# SolarCharger.net
KiCad netlist of a schematic drawn in Altium Designer
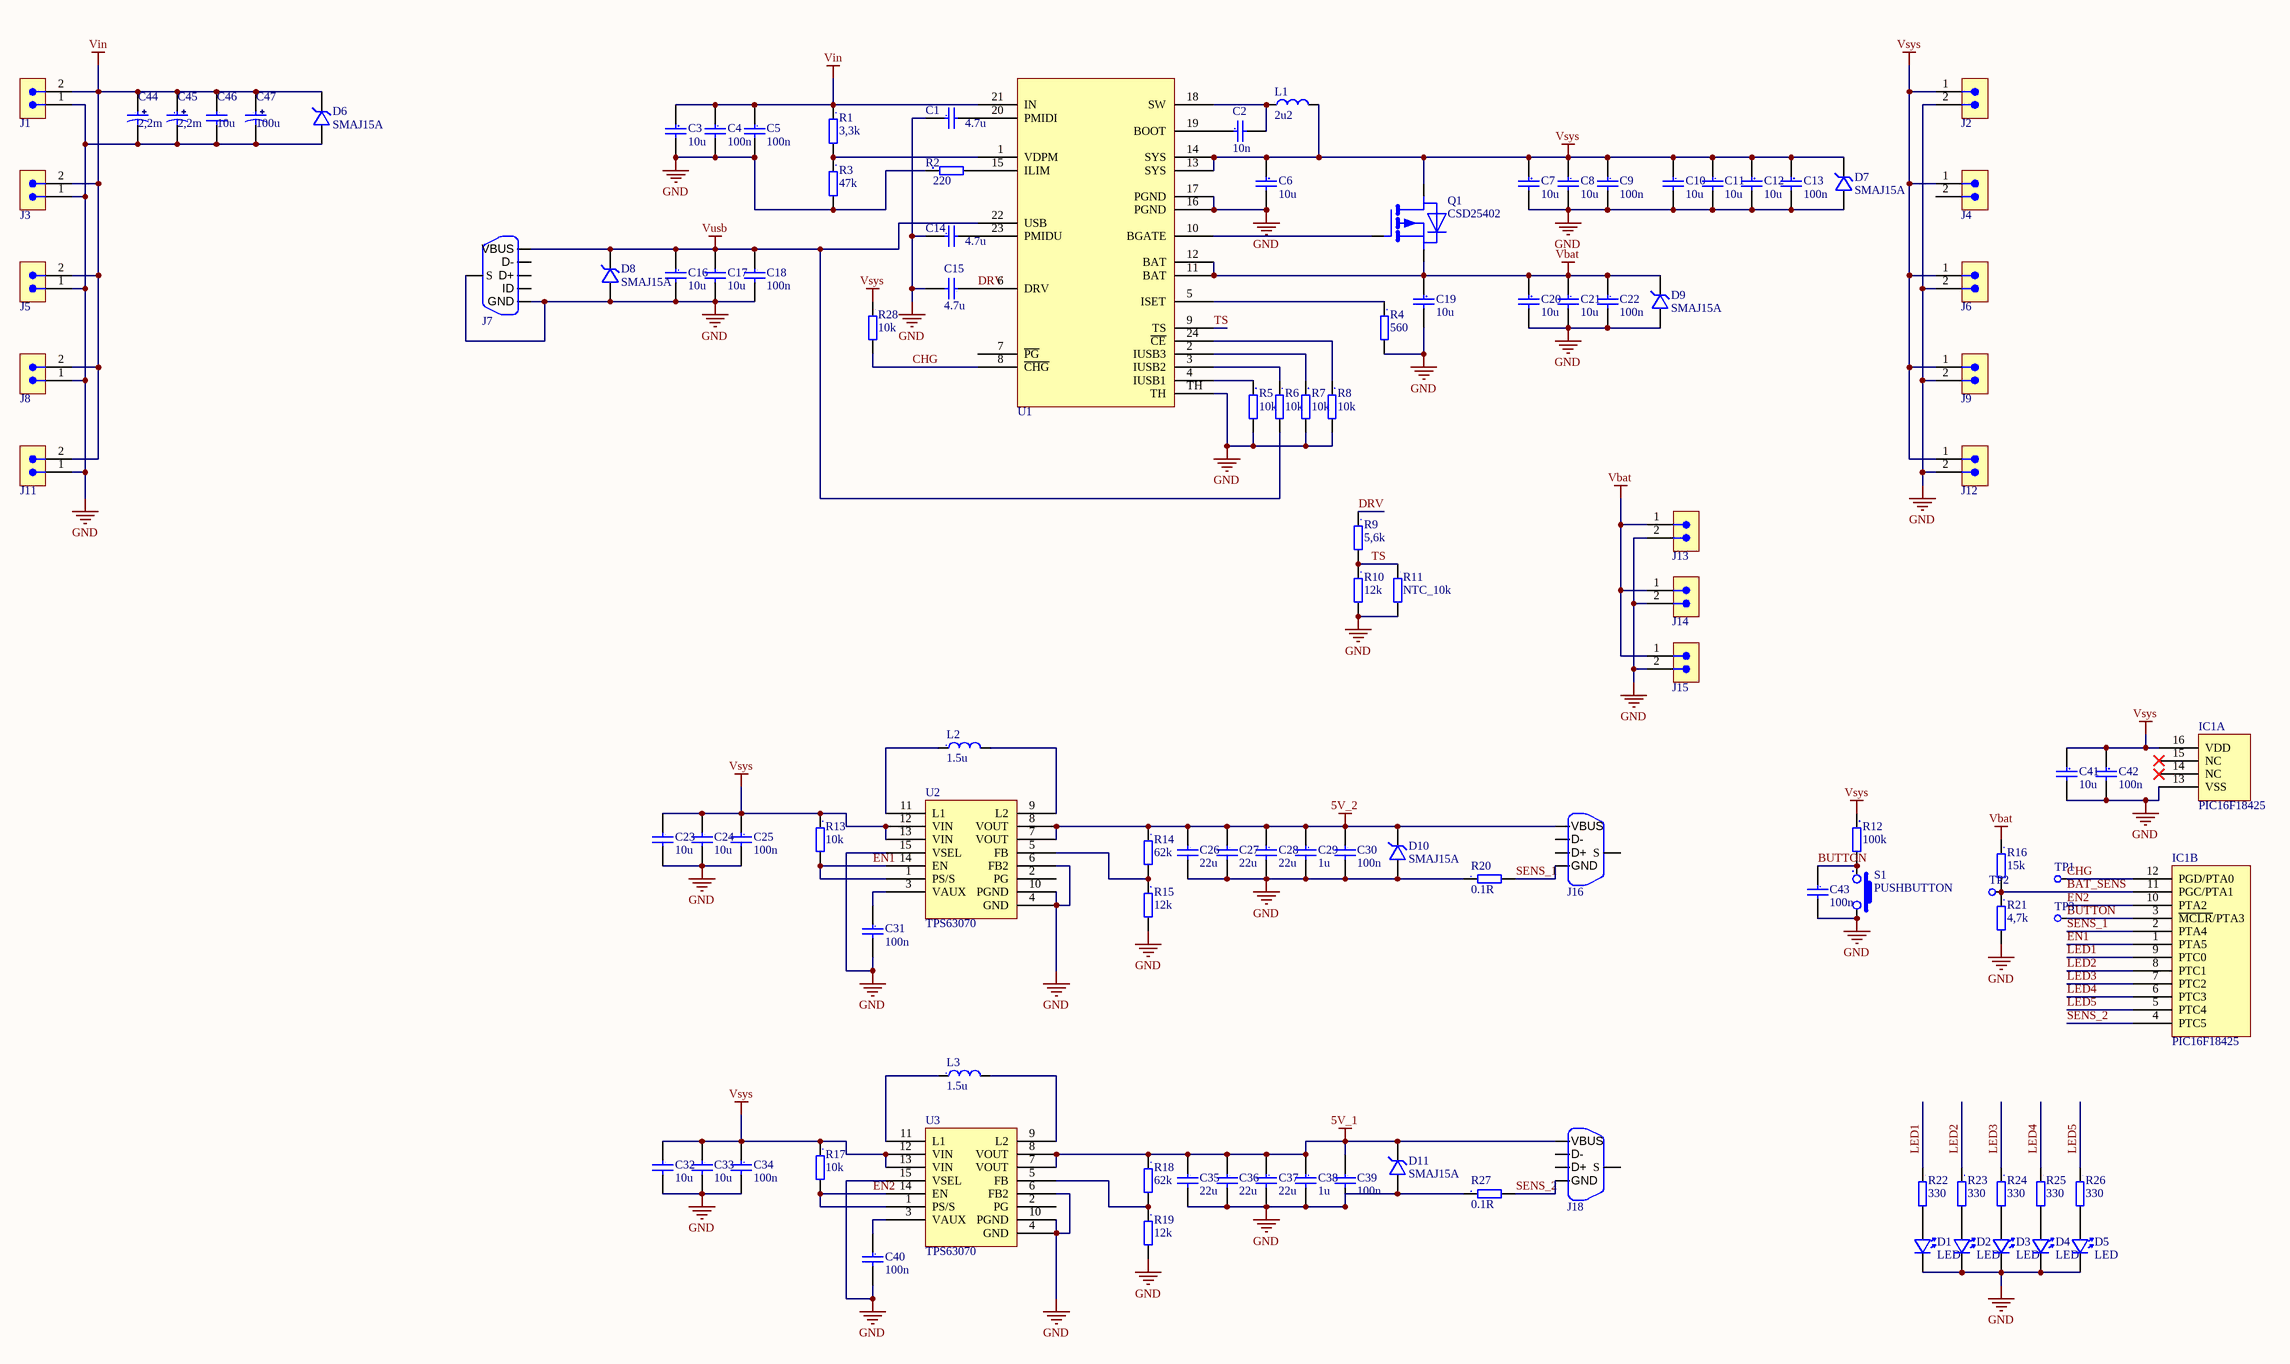
[diagram p0: SolarCharger.SchDoc]

(export (version "E")
  (design (tool "Eeschema 10.0.6"))
  (components
    (comp (ref "C1") (value "4.7u") (footprint "C0603_N") (libsource (lib "MyLib") (part "CAP")))
    (comp (ref "C2") (value "10n") (footprint "C0603_N") (libsource (lib "MyLib") (part "CAP")))
    (comp (ref "C3") (value "10u") (footprint "C0805_N") (libsource (lib "MyLib") (part "CAP")))
    (comp (ref "C4") (value "100n") (footprint "C0603_N") (libsource (lib "MyLib") (part "CAP")))
    (comp (ref "C5") (value "100n") (footprint "C0603_N") (libsource (lib "MyLib") (part "CAP")))
    (comp (ref "C6") (value "10u") (footprint "C0805_N") (libsource (lib "MyLib") (part "CAP")))
    (comp (ref "C7") (value "10u") (footprint "C0805_N") (libsource (lib "MyLib") (part "CAP")))
    (comp (ref "C8") (value "10u") (footprint "C0805_N") (libsource (lib "MyLib") (part "CAP")))
    (comp (ref "C9") (value "100n") (footprint "C0603_N") (libsource (lib "MyLib") (part "CAP")))
    (comp (ref "C10") (value "10u") (footprint "C0805_N") (libsource (lib "MyLib") (part "CAP")))
    (comp (ref "C11") (value "10u") (footprint "C0805_N") (libsource (lib "MyLib") (part "CAP")))
    (comp (ref "C12") (value "10u") (footprint "C0805_N") (libsource (lib "MyLib") (part "CAP")))
    (comp (ref "C13") (value "100n") (footprint "C0603_N") (libsource (lib "MyLib") (part "CAP")))
    (comp (ref "C14") (value "4.7u") (footprint "C0603_N") (libsource (lib "MyLib") (part "CAP")))
    (comp (ref "C15") (value "4.7u") (footprint "C0603_N") (libsource (lib "MyLib") (part "CAP")))
    (comp (ref "C16") (value "10u") (footprint "C0805_N") (libsource (lib "MyLib") (part "CAP")))
    (comp (ref "C17") (value "10u") (footprint "C0805_N") (libsource (lib "MyLib") (part "CAP")))
    (comp (ref "C18") (value "100n") (footprint "C0603_N") (libsource (lib "MyLib") (part "CAP")))
    (comp (ref "C19") (value "10u") (footprint "C0805_N") (libsource (lib "MyLib") (part "CAP")))
    (comp (ref "C20") (value "10u") (footprint "C0805_N") (libsource (lib "MyLib") (part "CAP")))
    (comp (ref "C21") (value "10u") (footprint "C0805_N") (libsource (lib "MyLib") (part "CAP")))
    (comp (ref "C22") (value "100n") (footprint "C0603_N") (libsource (lib "MyLib") (part "CAP")))
    (comp (ref "C23") (value "10u") (footprint "C0603_N") (libsource (lib "MyLib") (part "CAP")))
    (comp (ref "C24") (value "10u") (footprint "C0805_N") (libsource (lib "MyLib") (part "CAP")))
    (comp (ref "C25") (value "100n") (footprint "C0603_N") (libsource (lib "MyLib") (part "CAP")))
    (comp (ref "C26") (value "22u") (footprint "C0805_N") (libsource (lib "MyLib") (part "CAP")))
    (comp (ref "C27") (value "22u") (footprint "C0805_N") (libsource (lib "MyLib") (part "CAP")))
    (comp (ref "C28") (value "22u") (footprint "C0805_N") (libsource (lib "MyLib") (part "CAP")))
    (comp (ref "C29") (value "1u") (footprint "C0603_N") (libsource (lib "MyLib") (part "CAP")))
    (comp (ref "C30") (value "100n") (footprint "C0603_N") (libsource (lib "MyLib") (part "CAP")))
    (comp (ref "C31") (value "100n") (footprint "C0402_N") (libsource (lib "MyLib") (part "CAP")))
    (comp (ref "C32") (value "10u") (footprint "C0603_N") (libsource (lib "MyLib") (part "CAP")))
    (comp (ref "C33") (value "10u") (footprint "C0805_N") (libsource (lib "MyLib") (part "CAP")))
    (comp (ref "C34") (value "100n") (footprint "C0603_N") (libsource (lib "MyLib") (part "CAP")))
    (comp (ref "C35") (value "22u") (footprint "C0805_N") (libsource (lib "MyLib") (part "CAP")))
    (comp (ref "C36") (value "22u") (footprint "C0805_N") (libsource (lib "MyLib") (part "CAP")))
    (comp (ref "C37") (value "22u") (footprint "C0805_N") (libsource (lib "MyLib") (part "CAP")))
    (comp (ref "C38") (value "1u") (footprint "C0603_N") (libsource (lib "MyLib") (part "CAP")))
    (comp (ref "C39") (value "100n") (footprint "C0603_N") (libsource (lib "MyLib") (part "CAP")))
    (comp (ref "C40") (value "100n") (footprint "C0402_N") (libsource (lib "MyLib") (part "CAP")))
    (comp (ref "C41") (value "10u") (footprint "C0805_N") (libsource (lib "MyLib") (part "CAP")))
    (comp (ref "C42") (value "100n") (footprint "C0603_N") (libsource (lib "MyLib") (part "CAP")))
    (comp (ref "C43") (value "100n") (footprint "C0402_N") (libsource (lib "MyLib") (part "CAP")))
    (comp (ref "C44") (value "2,2m") (footprint "C592D_X") (libsource (lib "MyLib") (part "CAP_POL")))
    (comp (ref "C45") (value "2,2m") (footprint "C592D_X") (libsource (lib "MyLib") (part "CAP_POL")))
    (comp (ref "C46") (value "10u") (footprint "C0805_N") (libsource (lib "MyLib") (part "CAP")))
    (comp (ref "C47") (value "100u") (footprint "C_TR3D") (libsource (lib "MyLib") (part "CAP_POL")))
    (comp (ref "D1") (value "LED") (footprint "LED_0603") (libsource (lib "MyLib") (part "LED")))
    (comp (ref "D2") (value "LED") (footprint "LED_0603") (libsource (lib "MyLib") (part "LED")))
    (comp (ref "D3") (value "LED") (footprint "LED_0603") (libsource (lib "MyLib") (part "LED")))
    (comp (ref "D4") (value "LED") (footprint "LED_0603") (libsource (lib "MyLib") (part "LED")))
    (comp (ref "D5") (value "LED") (footprint "LED_0603") (libsource (lib "MyLib") (part "LED")))
    (comp (ref "D6") (value "SMAJ15A") (footprint "DO-214AC") (libsource (lib "MyLib") (part "DIODE_ZENER")))
    (comp (ref "D7") (value "SMAJ15A") (footprint "DO-214AC") (libsource (lib "MyLib") (part "DIODE_ZENER")))
    (comp (ref "D8") (value "SMAJ15A") (footprint "DO-214AC") (libsource (lib "MyLib") (part "DIODE_ZENER")))
    (comp (ref "D9") (value "SMAJ15A") (footprint "DO-214AC") (libsource (lib "MyLib") (part "DIODE_ZENER")))
    (comp (ref "D10") (value "SMAJ15A") (footprint "DO-214AC") (libsource (lib "MyLib") (part "DIODE_ZENER")))
    (comp (ref "D11") (value "SMAJ15A") (footprint "DO-214AC") (libsource (lib "MyLib") (part "DIODE_ZENER")))
    (comp (ref "IC1")
      (value "PIC16F18425")
      (footprint "UQFN-16")
      (description "PIC16F18425 chip with 16 pin lead")
      (libsource (lib "MyLib") (part "PIC16F18425"))
    )
    (comp (ref "J1")
      (value "~")
      (footprint "B2B-XH-A")
      (description "Socket")
      (libsource (lib "MyLib") (part "PINHDR_2X1"))
    )
    (comp (ref "J2")
      (value "~")
      (footprint "B2B-XH-A")
      (description "Socket")
      (libsource (lib "") (part "PINHDR_2X1_1"))
    )
    (comp (ref "J3")
      (value "~")
      (footprint "B2B-XH-A")
      (description "Socket")
      (libsource (lib "MyLib") (part "PINHDR_2X1"))
    )
    (comp (ref "J4")
      (value "~")
      (footprint "B2B-XH-A")
      (description "Socket")
      (libsource (lib "") (part "PINHDR_2X1_1"))
    )
    (comp (ref "J5")
      (value "~")
      (footprint "B2B-XH-A")
      (description "Socket")
      (libsource (lib "MyLib") (part "PINHDR_2X1"))
    )
    (comp (ref "J6")
      (value "~")
      (footprint "B2B-XH-A")
      (description "Socket")
      (libsource (lib "") (part "PINHDR_2X1_1"))
    )
    (comp (ref "J7")
      (value "USB_OTG")
      (footprint "WR-COM-629105136821")
      (libsource (lib "MyLib") (part "USB_OTG"))
    )
    (comp (ref "J8")
      (value "~")
      (footprint "B2B-XH-A")
      (description "Socket")
      (libsource (lib "MyLib") (part "PINHDR_2X1"))
    )
    (comp (ref "J9")
      (value "~")
      (footprint "B2B-XH-A")
      (description "Socket")
      (libsource (lib "") (part "PINHDR_2X1_1"))
    )
    (comp (ref "J11")
      (value "~")
      (footprint "B2B-XH-A")
      (description "Socket")
      (libsource (lib "MyLib") (part "PINHDR_2X1"))
    )
    (comp (ref "J12")
      (value "~")
      (footprint "B2B-XH-A")
      (description "Socket")
      (libsource (lib "") (part "PINHDR_2X1_1"))
    )
    (comp (ref "J13")
      (value "~")
      (footprint "B2B-XH-A")
      (description "Socket")
      (libsource (lib "") (part "PINHDR_2X1_1"))
    )
    (comp (ref "J14")
      (value "~")
      (footprint "B2B-XH-A")
      (description "Socket")
      (libsource (lib "") (part "PINHDR_2X1_1"))
    )
    (comp (ref "J15")
      (value "~")
      (footprint "B2B-XH-A")
      (description "Socket")
      (libsource (lib "") (part "PINHDR_2X1_1"))
    )
    (comp (ref "J16") (value "USB") (footprint "USB_TYPE_A_SOCK") (libsource (lib "MyLib") (part "USB")))
    (comp (ref "J18") (value "USB") (footprint "USB_TYPE_A_SOCK") (libsource (lib "MyLib") (part "USB")))
    (comp (ref "L1")
      (value "2u2")
      (footprint "SNR5040")
      (description "Inductor")
      (libsource (lib "MyLib") (part "IND"))
    )
    (comp (ref "L2")
      (value "1.5u")
      (footprint "IHLP2020")
      (description "Inductor")
      (libsource (lib "MyLib") (part "IND"))
    )
    (comp (ref "L3")
      (value "1.5u")
      (footprint "IHLP2020")
      (description "Inductor")
      (libsource (lib "MyLib") (part "IND"))
    )
    (comp (ref "Q1") (value "CSD25402") (footprint "DNH8") (libsource (lib "MyLib") (part "MOSFET_P")))
    (comp (ref "R1") (value "3,3k") (footprint "R0603_N") (libsource (lib "MyLib") (part "RES")))
    (comp (ref "R2") (value "220") (footprint "R0603_N") (libsource (lib "MyLib") (part "RES")))
    (comp (ref "R3") (value "47k") (footprint "R0603_N") (libsource (lib "MyLib") (part "RES")))
    (comp (ref "R4") (value "560") (footprint "R0603_N") (libsource (lib "MyLib") (part "RES")))
    (comp (ref "R5") (value "10k") (footprint "R0603_N") (libsource (lib "MyLib") (part "RES")))
    (comp (ref "R6") (value "10k") (footprint "R0603_N") (libsource (lib "MyLib") (part "RES")))
    (comp (ref "R7") (value "10k") (footprint "R0603_N") (libsource (lib "MyLib") (part "RES")))
    (comp (ref "R8") (value "10k") (footprint "R0603_N") (libsource (lib "MyLib") (part "RES")))
    (comp (ref "R9") (value "5,6k") (footprint "R0603_N") (libsource (lib "MyLib") (part "RES")))
    (comp (ref "R10") (value "12k") (footprint "R0603_N") (libsource (lib "MyLib") (part "RES")))
    (comp (ref "R11") (value "NTC_10k") (footprint "R0603_N") (libsource (lib "MyLib") (part "RES")))
    (comp (ref "R12") (value "100k") (footprint "R0402_N") (libsource (lib "MyLib") (part "RES")))
    (comp (ref "R13") (value "10k") (footprint "R0402_N") (libsource (lib "MyLib") (part "RES")))
    (comp (ref "R14") (value "62k") (footprint "R0603_N") (libsource (lib "MyLib") (part "RES")))
    (comp (ref "R15") (value "12k") (footprint "R0603_N") (libsource (lib "MyLib") (part "RES")))
    (comp (ref "R16") (value "15k") (footprint "R0603_N") (libsource (lib "MyLib") (part "RES")))
    (comp (ref "R17") (value "10k") (footprint "R0402_N") (libsource (lib "MyLib") (part "RES")))
    (comp (ref "R18") (value "62k") (footprint "R0603_N") (libsource (lib "MyLib") (part "RES")))
    (comp (ref "R19") (value "12k") (footprint "R0603_N") (libsource (lib "MyLib") (part "RES")))
    (comp (ref "R20") (value "0.1R") (footprint "R0805_N") (libsource (lib "MyLib") (part "RES")))
    (comp (ref "R21") (value "4,7k") (footprint "R0603_N") (libsource (lib "MyLib") (part "RES")))
    (comp (ref "R22") (value "330") (footprint "R0402_N") (libsource (lib "MyLib") (part "RES")))
    (comp (ref "R23") (value "330") (footprint "R0402_N") (libsource (lib "MyLib") (part "RES")))
    (comp (ref "R24") (value "330") (footprint "R0402_N") (libsource (lib "MyLib") (part "RES")))
    (comp (ref "R25") (value "330") (footprint "R0402_N") (libsource (lib "MyLib") (part "RES")))
    (comp (ref "R26") (value "330") (footprint "R0402_N") (libsource (lib "MyLib") (part "RES")))
    (comp (ref "R27") (value "0.1R") (footprint "R0805_N") (libsource (lib "MyLib") (part "RES")))
    (comp (ref "R28") (value "10k") (footprint "R0402_N") (libsource (lib "MyLib") (part "RES")))
    (comp (ref "S1")
      (value "PUSHBUTTON")
      (footprint "TACT6X6_SMD")
      (libsource (lib "MyLib") (part "PUSHBUTTON"))
    )
    (comp (ref "TP1") (value "TP") (footprint "TP_1MM") (libsource (lib "MyLib") (part "TP")))
    (comp (ref "TP2") (value "TP") (footprint "TP_1MM") (libsource (lib "MyLib") (part "TP")))
    (comp (ref "TP3") (value "TP") (footprint "TP_1MM") (libsource (lib "MyLib") (part "TP")))
    (comp (ref "U1")
      (value "BQ24166")
      (footprint "VQFN-24")
      (description "2.5A, Dual-Input, Single Cell Switch Mode Li-Ion Battery Charger with Power Path\r\nManagement")
      (libsource (lib "MyLib") (part "BQ24166"))
    )
    (comp (ref "U2")
      (value "TPS63070")
      (footprint "TPS63070")
      (description "2-V to 16-V Buck-Boost Converter With 3.6-A Switch Current")
      (libsource (lib "MyLib") (part "TPS63070"))
    )
    (comp (ref "U3")
      (value "TPS63070")
      (footprint "TPS63070")
      (description "2-V to 16-V Buck-Boost Converter With 3.6-A Switch Current")
      (libsource (lib "MyLib") (part "TPS63070"))
    )
  )
  (nets
    (net (code "1") (name "/BAT_SENS") (class "Default")
      (node (ref "IC1") (pin "11") (pinfunction "PGC/PTA1_11") (pintype "passive"))
      (node (ref "R16") (pin "2") (pinfunction "2_2") (pintype "passive"))
      (node (ref "R21") (pin "1") (pinfunction "1_1") (pintype "passive"))
      (node (ref "TP2") (pin "1") (pinfunction "1_1") (pintype "passive"))
    )
    (net (code "2") (name "/BUTTON") (class "Default")
      (node (ref "C43") (pin "1") (pinfunction "1_1") (pintype "passive"))
      (node (ref "IC1") (pin "3") (pinfunction "~{MCLR}/PTA3_3") (pintype "passive"))
      (node (ref "R12") (pin "2") (pinfunction "2_2") (pintype "passive"))
      (node (ref "S1") (pin "1") (pinfunction "1_1") (pintype "passive"))
      (node (ref "TP3") (pin "1") (pinfunction "1_1") (pintype "passive"))
    )
    (net (code "3") (name "/CHG") (class "Default")
      (node (ref "IC1") (pin "12") (pinfunction "PGD/PTA0_12") (pintype "passive"))
      (node (ref "R28") (pin "2") (pinfunction "2_2") (pintype "passive"))
      (node (ref "TP1") (pin "1") (pinfunction "1_1") (pintype "passive"))
      (node (ref "U1") (pin "8") (pinfunction "~{CHG}_8") (pintype "passive"))
    )
    (net (code "4") (name "/DRV") (class "Default")
      (node (ref "C15") (pin "1") (pinfunction "1_1") (pintype "passive"))
      (node (ref "R9") (pin "1") (pinfunction "1_1") (pintype "passive"))
      (node (ref "U1") (pin "6") (pinfunction "DRV_6") (pintype "passive"))
    )
    (net (code "5") (name "/EN1") (class "Default")
      (node (ref "IC1") (pin "1") (pinfunction "PTA5_1") (pintype "passive"))
      (node (ref "R13") (pin "2") (pinfunction "2_2") (pintype "passive"))
      (node (ref "U2") (pin "1") (pinfunction "PS/S_1") (pintype "passive"))
      (node (ref "U2") (pin "14") (pinfunction "EN_14") (pintype "passive"))
    )
    (net (code "6") (name "/EN2") (class "Default")
      (node (ref "IC1") (pin "10") (pinfunction "PTA2_10") (pintype "passive"))
      (node (ref "R17") (pin "2") (pinfunction "2_2") (pintype "passive"))
      (node (ref "U3") (pin "1") (pinfunction "PS/S_1") (pintype "passive"))
      (node (ref "U3") (pin "14") (pinfunction "EN_14") (pintype "passive"))
    )
    (net (code "7") (name "/LED1") (class "Default")
      (node (ref "IC1") (pin "9") (pinfunction "PTC0_9") (pintype "passive"))
      (node (ref "R22") (pin "1") (pinfunction "1_1") (pintype "passive"))
    )
    (net (code "8") (name "/LED2") (class "Default")
      (node (ref "IC1") (pin "8") (pinfunction "PTC1_8") (pintype "passive"))
      (node (ref "R23") (pin "1") (pinfunction "1_1") (pintype "passive"))
    )
    (net (code "9") (name "/LED3") (class "Default")
      (node (ref "IC1") (pin "7") (pinfunction "PTC2_7") (pintype "passive"))
      (node (ref "R24") (pin "1") (pinfunction "1_1") (pintype "passive"))
    )
    (net (code "10") (name "/LED4") (class "Default")
      (node (ref "IC1") (pin "6") (pinfunction "PTC3_6") (pintype "passive"))
      (node (ref "R25") (pin "1") (pinfunction "1_1") (pintype "passive"))
    )
    (net (code "11") (name "/LED5") (class "Default")
      (node (ref "IC1") (pin "5") (pinfunction "PTC4_5") (pintype "passive"))
      (node (ref "R26") (pin "1") (pinfunction "1_1") (pintype "passive"))
    )
    (net (code "12") (name "/SENS_1") (class "Default")
      (node (ref "IC1") (pin "2") (pinfunction "PTA4_2") (pintype "passive"))
      (node (ref "J16") (pin "GND") (pinfunction "GND_GND") (pintype "passive"))
      (node (ref "R20") (pin "2") (pinfunction "2_2") (pintype "passive"))
    )
    (net (code "13") (name "/SENS_2") (class "Default")
      (node (ref "IC1") (pin "4") (pinfunction "PTC5_4") (pintype "passive"))
      (node (ref "J18") (pin "GND") (pinfunction "GND_GND") (pintype "passive"))
      (node (ref "R27") (pin "2") (pinfunction "2_2") (pintype "passive"))
    )
    (net (code "14") (name "/TS") (class "Default")
      (node (ref "R10") (pin "1") (pinfunction "1_1") (pintype "passive"))
      (node (ref "R11") (pin "1") (pinfunction "1_1") (pintype "passive"))
      (node (ref "R9") (pin "2") (pinfunction "2_2") (pintype "passive"))
      (node (ref "U1") (pin "9") (pinfunction "TS_9") (pintype "passive"))
    )
    (net (code "15") (name "5V_1") (class "Default")
      (node (ref "C35") (pin "1") (pinfunction "1_1") (pintype "passive"))
      (node (ref "C36") (pin "1") (pinfunction "1_1") (pintype "passive"))
      (node (ref "C37") (pin "1") (pinfunction "1_1") (pintype "passive"))
      (node (ref "C38") (pin "1") (pinfunction "1_1") (pintype "passive"))
      (node (ref "C39") (pin "1") (pinfunction "1_1") (pintype "passive"))
      (node (ref "D11") (pin "C") (pinfunction "C_C") (pintype "passive"))
      (node (ref "J18") (pin "VBUS") (pinfunction "VBUS_VBUS") (pintype "passive"))
      (node (ref "R18") (pin "1") (pinfunction "1_1") (pintype "passive"))
      (node (ref "U3") (pin "7") (pinfunction "VOUT_7") (pintype "passive"))
      (node (ref "U3") (pin "8") (pinfunction "VOUT_8") (pintype "passive"))
    )
    (net (code "16") (name "5V_2") (class "Default")
      (node (ref "C26") (pin "1") (pinfunction "1_1") (pintype "passive"))
      (node (ref "C27") (pin "1") (pinfunction "1_1") (pintype "passive"))
      (node (ref "C28") (pin "1") (pinfunction "1_1") (pintype "passive"))
      (node (ref "C29") (pin "1") (pinfunction "1_1") (pintype "passive"))
      (node (ref "C30") (pin "1") (pinfunction "1_1") (pintype "passive"))
      (node (ref "D10") (pin "C") (pinfunction "C_C") (pintype "passive"))
      (node (ref "J16") (pin "VBUS") (pinfunction "VBUS_VBUS") (pintype "passive"))
      (node (ref "R14") (pin "1") (pinfunction "1_1") (pintype "passive"))
      (node (ref "U2") (pin "7") (pinfunction "VOUT_7") (pintype "passive"))
      (node (ref "U2") (pin "8") (pinfunction "VOUT_8") (pintype "passive"))
    )
    (net (code "17") (name "GND") (class "Default")
      (node (ref "C1") (pin "1") (pinfunction "1_1") (pintype "passive"))
      (node (ref "C10") (pin "2") (pinfunction "2_2") (pintype "passive"))
      (node (ref "C11") (pin "2") (pinfunction "2_2") (pintype "passive"))
      (node (ref "C12") (pin "2") (pinfunction "2_2") (pintype "passive"))
      (node (ref "C13") (pin "2") (pinfunction "2_2") (pintype "passive"))
      (node (ref "C14") (pin "1") (pinfunction "1_1") (pintype "passive"))
      (node (ref "C15") (pin "2") (pinfunction "2_2") (pintype "passive"))
      (node (ref "C16") (pin "2") (pinfunction "2_2") (pintype "passive"))
      (node (ref "C17") (pin "2") (pinfunction "2_2") (pintype "passive"))
      (node (ref "C18") (pin "2") (pinfunction "2_2") (pintype "passive"))
      (node (ref "C19") (pin "2") (pinfunction "2_2") (pintype "passive"))
      (node (ref "C20") (pin "2") (pinfunction "2_2") (pintype "passive"))
      (node (ref "C21") (pin "2") (pinfunction "2_2") (pintype "passive"))
      (node (ref "C22") (pin "2") (pinfunction "2_2") (pintype "passive"))
      (node (ref "C23") (pin "2") (pinfunction "2_2") (pintype "passive"))
      (node (ref "C24") (pin "2") (pinfunction "2_2") (pintype "passive"))
      (node (ref "C25") (pin "2") (pinfunction "2_2") (pintype "passive"))
      (node (ref "C26") (pin "2") (pinfunction "2_2") (pintype "passive"))
      (node (ref "C27") (pin "2") (pinfunction "2_2") (pintype "passive"))
      (node (ref "C28") (pin "2") (pinfunction "2_2") (pintype "passive"))
      (node (ref "C29") (pin "2") (pinfunction "2_2") (pintype "passive"))
      (node (ref "C3") (pin "2") (pinfunction "2_2") (pintype "passive"))
      (node (ref "C30") (pin "2") (pinfunction "2_2") (pintype "passive"))
      (node (ref "C31") (pin "2") (pinfunction "2_2") (pintype "passive"))
      (node (ref "C32") (pin "2") (pinfunction "2_2") (pintype "passive"))
      (node (ref "C33") (pin "2") (pinfunction "2_2") (pintype "passive"))
      (node (ref "C34") (pin "2") (pinfunction "2_2") (pintype "passive"))
      (node (ref "C35") (pin "2") (pinfunction "2_2") (pintype "passive"))
      (node (ref "C36") (pin "2") (pinfunction "2_2") (pintype "passive"))
      (node (ref "C37") (pin "2") (pinfunction "2_2") (pintype "passive"))
      (node (ref "C38") (pin "2") (pinfunction "2_2") (pintype "passive"))
      (node (ref "C39") (pin "2") (pinfunction "2_2") (pintype "passive"))
      (node (ref "C4") (pin "2") (pinfunction "2_2") (pintype "passive"))
      (node (ref "C40") (pin "2") (pinfunction "2_2") (pintype "passive"))
      (node (ref "C41") (pin "2") (pinfunction "2_2") (pintype "passive"))
      (node (ref "C42") (pin "2") (pinfunction "2_2") (pintype "passive"))
      (node (ref "C43") (pin "2") (pinfunction "2_2") (pintype "passive"))
      (node (ref "C44") (pin "N") (pinfunction "N_N") (pintype "passive"))
      (node (ref "C45") (pin "N") (pinfunction "N_N") (pintype "passive"))
      (node (ref "C46") (pin "2") (pinfunction "2_2") (pintype "passive"))
      (node (ref "C47") (pin "N") (pinfunction "N_N") (pintype "passive"))
      (node (ref "C5") (pin "2") (pinfunction "2_2") (pintype "passive"))
      (node (ref "C6") (pin "2") (pinfunction "2_2") (pintype "passive"))
      (node (ref "C7") (pin "2") (pinfunction "2_2") (pintype "passive"))
      (node (ref "C8") (pin "2") (pinfunction "2_2") (pintype "passive"))
      (node (ref "C9") (pin "2") (pinfunction "2_2") (pintype "passive"))
      (node (ref "D1") (pin "K") (pinfunction "K_K") (pintype "passive"))
      (node (ref "D10") (pin "A") (pinfunction "A_A") (pintype "passive"))
      (node (ref "D11") (pin "A") (pinfunction "A_A") (pintype "passive"))
      (node (ref "D2") (pin "K") (pinfunction "K_K") (pintype "passive"))
      (node (ref "D3") (pin "K") (pinfunction "K_K") (pintype "passive"))
      (node (ref "D4") (pin "K") (pinfunction "K_K") (pintype "passive"))
      (node (ref "D5") (pin "K") (pinfunction "K_K") (pintype "passive"))
      (node (ref "D6") (pin "A") (pinfunction "A_A") (pintype "passive"))
      (node (ref "D7") (pin "A") (pinfunction "A_A") (pintype "passive"))
      (node (ref "D8") (pin "A") (pinfunction "A_A") (pintype "passive"))
      (node (ref "D9") (pin "A") (pinfunction "A_A") (pintype "passive"))
      (node (ref "IC1") (pin "13") (pinfunction "VSS_13") (pintype "passive"))
      (node (ref "J1") (pin "1") (pinfunction "1_1") (pintype "passive"))
      (node (ref "J11") (pin "1") (pinfunction "1_1") (pintype "passive"))
      (node (ref "J12") (pin "2") (pinfunction "2_2") (pintype "passive"))
      (node (ref "J13") (pin "2") (pinfunction "2_2") (pintype "passive"))
      (node (ref "J14") (pin "2") (pinfunction "2_2") (pintype "passive"))
      (node (ref "J15") (pin "2") (pinfunction "2_2") (pintype "passive"))
      (node (ref "J2") (pin "2") (pinfunction "2_2") (pintype "passive"))
      (node (ref "J3") (pin "1") (pinfunction "1_1") (pintype "passive"))
      (node (ref "J5") (pin "1") (pinfunction "1_1") (pintype "passive"))
      (node (ref "J6") (pin "2") (pinfunction "2_2") (pintype "passive"))
      (node (ref "J7") (pin "GND") (pinfunction "GND_GND") (pintype "passive"))
      (node (ref "J7") (pin "S") (pinfunction "S_S") (pintype "passive"))
      (node (ref "J8") (pin "1") (pinfunction "1_1") (pintype "passive"))
      (node (ref "J9") (pin "2") (pinfunction "2_2") (pintype "passive"))
      (node (ref "R10") (pin "2") (pinfunction "2_2") (pintype "passive"))
      (node (ref "R11") (pin "2") (pinfunction "2_2") (pintype "passive"))
      (node (ref "R15") (pin "2") (pinfunction "2_2") (pintype "passive"))
      (node (ref "R19") (pin "2") (pinfunction "2_2") (pintype "passive"))
      (node (ref "R2") (pin "1") (pinfunction "1_1") (pintype "passive"))
      (node (ref "R20") (pin "1") (pinfunction "1_1") (pintype "passive"))
      (node (ref "R21") (pin "2") (pinfunction "2_2") (pintype "passive"))
      (node (ref "R27") (pin "1") (pinfunction "1_1") (pintype "passive"))
      (node (ref "R3") (pin "2") (pinfunction "2_2") (pintype "passive"))
      (node (ref "R4") (pin "2") (pinfunction "2_2") (pintype "passive"))
      (node (ref "R5") (pin "2") (pinfunction "2_2") (pintype "passive"))
      (node (ref "R7") (pin "2") (pinfunction "2_2") (pintype "passive"))
      (node (ref "R8") (pin "2") (pinfunction "2_2") (pintype "passive"))
      (node (ref "S1") (pin "2") (pinfunction "2_2") (pintype "passive"))
      (node (ref "U1") (pin "16") (pinfunction "PGND_16") (pintype "passive"))
      (node (ref "U1") (pin "17") (pinfunction "PGND_17") (pintype "passive"))
      (node (ref "U1") (pin "TH") (pinfunction "TH_TH") (pintype "passive"))
      (node (ref "U2") (pin "10") (pinfunction "PGND_10") (pintype "passive"))
      (node (ref "U2") (pin "15") (pinfunction "VSEL_15") (pintype "passive"))
      (node (ref "U2") (pin "4") (pinfunction "GND_4") (pintype "passive"))
      (node (ref "U2") (pin "6") (pinfunction "FB2_6") (pintype "passive"))
      (node (ref "U3") (pin "10") (pinfunction "PGND_10") (pintype "passive"))
      (node (ref "U3") (pin "15") (pinfunction "VSEL_15") (pintype "passive"))
      (node (ref "U3") (pin "4") (pinfunction "GND_4") (pintype "passive"))
      (node (ref "U3") (pin "6") (pinfunction "FB2_6") (pintype "passive"))
    )
    (net (code "18") (name "Net-(D1-PadA)") (class "Default")
      (node (ref "D1") (pin "A") (pinfunction "A_A") (pintype "passive"))
      (node (ref "R22") (pin "2") (pinfunction "2_2") (pintype "passive"))
    )
    (net (code "19") (name "Net-(D2-PadA)") (class "Default")
      (node (ref "D2") (pin "A") (pinfunction "A_A") (pintype "passive"))
      (node (ref "R23") (pin "2") (pinfunction "2_2") (pintype "passive"))
    )
    (net (code "20") (name "Net-(D3-PadA)") (class "Default")
      (node (ref "D3") (pin "A") (pinfunction "A_A") (pintype "passive"))
      (node (ref "R24") (pin "2") (pinfunction "2_2") (pintype "passive"))
    )
    (net (code "21") (name "Net-(D4-PadA)") (class "Default")
      (node (ref "D4") (pin "A") (pinfunction "A_A") (pintype "passive"))
      (node (ref "R25") (pin "2") (pinfunction "2_2") (pintype "passive"))
    )
    (net (code "22") (name "Net-(D5-PadA)") (class "Default")
      (node (ref "D5") (pin "A") (pinfunction "A_A") (pintype "passive"))
      (node (ref "R26") (pin "2") (pinfunction "2_2") (pintype "passive"))
    )
    (net (code "23") (name "Net-(U1-BGATE)") (class "Default")
      (node (ref "Q1") (pin "G") (pinfunction "G_G") (pintype "passive"))
      (node (ref "U1") (pin "10") (pinfunction "BGATE_10") (pintype "passive"))
    )
    (net (code "24") (name "Net-(U1-BOOT)") (class "Default")
      (node (ref "C2") (pin "1") (pinfunction "1_1") (pintype "passive"))
      (node (ref "U1") (pin "19") (pinfunction "BOOT_19") (pintype "passive"))
    )
    (net (code "25") (name "Net-(U1-ILIM)") (class "Default")
      (node (ref "R2") (pin "2") (pinfunction "2_2") (pintype "passive"))
      (node (ref "U1") (pin "15") (pinfunction "ILIM_15") (pintype "passive"))
    )
    (net (code "26") (name "Net-(U1-ISET)") (class "Default")
      (node (ref "R4") (pin "1") (pinfunction "1_1") (pintype "passive"))
      (node (ref "U1") (pin "5") (pinfunction "ISET_5") (pintype "passive"))
    )
    (net (code "27") (name "Net-(U1-IUSB1)") (class "Default")
      (node (ref "R5") (pin "1") (pinfunction "1_1") (pintype "passive"))
      (node (ref "U1") (pin "4") (pinfunction "IUSB1_4") (pintype "passive"))
    )
    (net (code "28") (name "Net-(U1-IUSB2)") (class "Default")
      (node (ref "R6") (pin "1") (pinfunction "1_1") (pintype "passive"))
      (node (ref "U1") (pin "3") (pinfunction "IUSB2_3") (pintype "passive"))
    )
    (net (code "29") (name "Net-(U1-IUSB3)") (class "Default")
      (node (ref "R7") (pin "1") (pinfunction "1_1") (pintype "passive"))
      (node (ref "U1") (pin "2") (pinfunction "IUSB3_2") (pintype "passive"))
    )
    (net (code "30") (name "Net-(U1-PMIDI)") (class "Default")
      (node (ref "C1") (pin "2") (pinfunction "2_2") (pintype "passive"))
      (node (ref "U1") (pin "20") (pinfunction "PMIDI_20") (pintype "passive"))
    )
    (net (code "31") (name "Net-(U1-PMIDU)") (class "Default")
      (node (ref "C14") (pin "2") (pinfunction "2_2") (pintype "passive"))
      (node (ref "U1") (pin "23") (pinfunction "PMIDU_23") (pintype "passive"))
    )
    (net (code "32") (name "Net-(U1-SW)") (class "Default")
      (node (ref "C2") (pin "2") (pinfunction "2_2") (pintype "passive"))
      (node (ref "L1") (pin "1") (pinfunction "1_1") (pintype "passive"))
      (node (ref "U1") (pin "18") (pinfunction "SW_18") (pintype "passive"))
    )
    (net (code "33") (name "Net-(U1-VDPM)") (class "Default")
      (node (ref "R1") (pin "2") (pinfunction "2_2") (pintype "passive"))
      (node (ref "R3") (pin "1") (pinfunction "1_1") (pintype "passive"))
      (node (ref "U1") (pin "1") (pinfunction "VDPM_1") (pintype "passive"))
    )
    (net (code "34") (name "Net-(U1-~{CE})") (class "Default")
      (node (ref "R8") (pin "1") (pinfunction "1_1") (pintype "passive"))
      (node (ref "U1") (pin "24") (pinfunction "~{CE}_24") (pintype "passive"))
    )
    (net (code "35") (name "Net-(U2-FB)") (class "Default")
      (node (ref "R14") (pin "2") (pinfunction "2_2") (pintype "passive"))
      (node (ref "R15") (pin "1") (pinfunction "1_1") (pintype "passive"))
      (node (ref "U2") (pin "5") (pinfunction "FB_5") (pintype "passive"))
    )
    (net (code "36") (name "Net-(U2-L1)") (class "Default")
      (node (ref "L2") (pin "1") (pinfunction "1_1") (pintype "passive"))
      (node (ref "U2") (pin "11") (pinfunction "L1_11") (pintype "passive"))
    )
    (net (code "37") (name "Net-(U2-L2)") (class "Default")
      (node (ref "L2") (pin "2") (pinfunction "2_2") (pintype "passive"))
      (node (ref "U2") (pin "9") (pinfunction "L2_9") (pintype "passive"))
    )
    (net (code "38") (name "Net-(U2-VAUX)") (class "Default")
      (node (ref "C31") (pin "1") (pinfunction "1_1") (pintype "passive"))
      (node (ref "U2") (pin "3") (pinfunction "VAUX_3") (pintype "passive"))
    )
    (net (code "39") (name "Net-(U3-FB)") (class "Default")
      (node (ref "R18") (pin "2") (pinfunction "2_2") (pintype "passive"))
      (node (ref "R19") (pin "1") (pinfunction "1_1") (pintype "passive"))
      (node (ref "U3") (pin "5") (pinfunction "FB_5") (pintype "passive"))
    )
    (net (code "40") (name "Net-(U3-L1)") (class "Default")
      (node (ref "L3") (pin "1") (pinfunction "1_1") (pintype "passive"))
      (node (ref "U3") (pin "11") (pinfunction "L1_11") (pintype "passive"))
    )
    (net (code "41") (name "Net-(U3-L2)") (class "Default")
      (node (ref "L3") (pin "2") (pinfunction "2_2") (pintype "passive"))
      (node (ref "U3") (pin "9") (pinfunction "L2_9") (pintype "passive"))
    )
    (net (code "42") (name "Net-(U3-VAUX)") (class "Default")
      (node (ref "C40") (pin "1") (pinfunction "1_1") (pintype "passive"))
      (node (ref "U3") (pin "3") (pinfunction "VAUX_3") (pintype "passive"))
    )
    (net (code "43") (name "Vbat") (class "Default")
      (node (ref "C19") (pin "1") (pinfunction "1_1") (pintype "passive"))
      (node (ref "C20") (pin "1") (pinfunction "1_1") (pintype "passive"))
      (node (ref "C21") (pin "1") (pinfunction "1_1") (pintype "passive"))
      (node (ref "C22") (pin "1") (pinfunction "1_1") (pintype "passive"))
      (node (ref "D9") (pin "C") (pinfunction "C_C") (pintype "passive"))
      (node (ref "J13") (pin "1") (pinfunction "1_1") (pintype "passive"))
      (node (ref "J14") (pin "1") (pinfunction "1_1") (pintype "passive"))
      (node (ref "J15") (pin "1") (pinfunction "1_1") (pintype "passive"))
      (node (ref "Q1") (pin "S") (pinfunction "S_S") (pintype "passive"))
      (node (ref "R16") (pin "1") (pinfunction "1_1") (pintype "passive"))
      (node (ref "U1") (pin "11") (pinfunction "BAT_11") (pintype "passive"))
      (node (ref "U1") (pin "12") (pinfunction "BAT_12") (pintype "passive"))
    )
    (net (code "44") (name "Vin") (class "Default")
      (node (ref "C3") (pin "1") (pinfunction "1_1") (pintype "passive"))
      (node (ref "C4") (pin "1") (pinfunction "1_1") (pintype "passive"))
      (node (ref "C44") (pin "P") (pinfunction "P_P") (pintype "passive"))
      (node (ref "C45") (pin "P") (pinfunction "P_P") (pintype "passive"))
      (node (ref "C46") (pin "1") (pinfunction "1_1") (pintype "passive"))
      (node (ref "C47") (pin "P") (pinfunction "P_P") (pintype "passive"))
      (node (ref "C5") (pin "1") (pinfunction "1_1") (pintype "passive"))
      (node (ref "D6") (pin "C") (pinfunction "C_C") (pintype "passive"))
      (node (ref "J1") (pin "2") (pinfunction "2_2") (pintype "passive"))
      (node (ref "J11") (pin "2") (pinfunction "2_2") (pintype "passive"))
      (node (ref "J3") (pin "2") (pinfunction "2_2") (pintype "passive"))
      (node (ref "J5") (pin "2") (pinfunction "2_2") (pintype "passive"))
      (node (ref "J8") (pin "2") (pinfunction "2_2") (pintype "passive"))
      (node (ref "R1") (pin "1") (pinfunction "1_1") (pintype "passive"))
      (node (ref "U1") (pin "21") (pinfunction "IN_21") (pintype "passive"))
    )
    (net (code "45") (name "Vsys") (class "Default")
      (node (ref "C10") (pin "1") (pinfunction "1_1") (pintype "passive"))
      (node (ref "C11") (pin "1") (pinfunction "1_1") (pintype "passive"))
      (node (ref "C12") (pin "1") (pinfunction "1_1") (pintype "passive"))
      (node (ref "C13") (pin "1") (pinfunction "1_1") (pintype "passive"))
      (node (ref "C23") (pin "1") (pinfunction "1_1") (pintype "passive"))
      (node (ref "C24") (pin "1") (pinfunction "1_1") (pintype "passive"))
      (node (ref "C25") (pin "1") (pinfunction "1_1") (pintype "passive"))
      (node (ref "C32") (pin "1") (pinfunction "1_1") (pintype "passive"))
      (node (ref "C33") (pin "1") (pinfunction "1_1") (pintype "passive"))
      (node (ref "C34") (pin "1") (pinfunction "1_1") (pintype "passive"))
      (node (ref "C41") (pin "1") (pinfunction "1_1") (pintype "passive"))
      (node (ref "C42") (pin "1") (pinfunction "1_1") (pintype "passive"))
      (node (ref "C6") (pin "1") (pinfunction "1_1") (pintype "passive"))
      (node (ref "C7") (pin "1") (pinfunction "1_1") (pintype "passive"))
      (node (ref "C8") (pin "1") (pinfunction "1_1") (pintype "passive"))
      (node (ref "C9") (pin "1") (pinfunction "1_1") (pintype "passive"))
      (node (ref "D7") (pin "C") (pinfunction "C_C") (pintype "passive"))
      (node (ref "IC1") (pin "16") (pinfunction "VDD_16") (pintype "passive"))
      (node (ref "J12") (pin "1") (pinfunction "1_1") (pintype "passive"))
      (node (ref "J2") (pin "1") (pinfunction "1_1") (pintype "passive"))
      (node (ref "J4") (pin "1") (pinfunction "1_1") (pintype "passive"))
      (node (ref "J6") (pin "1") (pinfunction "1_1") (pintype "passive"))
      (node (ref "J9") (pin "1") (pinfunction "1_1") (pintype "passive"))
      (node (ref "L1") (pin "2") (pinfunction "2_2") (pintype "passive"))
      (node (ref "Q1") (pin "D") (pinfunction "D_D") (pintype "passive"))
      (node (ref "R12") (pin "1") (pinfunction "1_1") (pintype "passive"))
      (node (ref "R13") (pin "1") (pinfunction "1_1") (pintype "passive"))
      (node (ref "R17") (pin "1") (pinfunction "1_1") (pintype "passive"))
      (node (ref "R28") (pin "1") (pinfunction "1_1") (pintype "passive"))
      (node (ref "U1") (pin "13") (pinfunction "SYS_13") (pintype "passive"))
      (node (ref "U1") (pin "14") (pinfunction "SYS_14") (pintype "passive"))
      (node (ref "U2") (pin "12") (pinfunction "VIN_12") (pintype "passive"))
      (node (ref "U2") (pin "13") (pinfunction "VIN_13") (pintype "passive"))
      (node (ref "U3") (pin "12") (pinfunction "VIN_12") (pintype "passive"))
      (node (ref "U3") (pin "13") (pinfunction "VIN_13") (pintype "passive"))
    )
    (net (code "46") (name "Vusb") (class "Default")
      (node (ref "C16") (pin "1") (pinfunction "1_1") (pintype "passive"))
      (node (ref "C17") (pin "1") (pinfunction "1_1") (pintype "passive"))
      (node (ref "C18") (pin "1") (pinfunction "1_1") (pintype "passive"))
      (node (ref "D8") (pin "C") (pinfunction "C_C") (pintype "passive"))
      (node (ref "J7") (pin "VBUS") (pinfunction "VBUS_VBUS") (pintype "passive"))
      (node (ref "R6") (pin "2") (pinfunction "2_2") (pintype "passive"))
      (node (ref "U1") (pin "22") (pinfunction "USB_22") (pintype "passive"))
    )
    (net (code "47") (name "unconnected-(IC1A-NC-Pad14)") (class "Default")
      (node (ref "IC1") (pin "14") (pinfunction "NC_14") (pintype "passive+no_connect"))
    )
    (net (code "48") (name "unconnected-(IC1A-NC-Pad15)") (class "Default")
      (node (ref "IC1") (pin "15") (pinfunction "NC_15") (pintype "passive+no_connect"))
    )
    (net (code "49") (name "unconnected-(J4-Pad2)") (class "Default")
      (node (ref "J4") (pin "2") (pinfunction "2_2") (pintype "passive"))
    )
    (net (code "50") (name "unconnected-(J7-D+-PadD_P)") (class "Default")
      (node (ref "J7") (pin "D_P") (pinfunction "D+_D_P") (pintype "passive"))
    )
    (net (code "51") (name "unconnected-(J7-D--PadD_N)") (class "Default")
      (node (ref "J7") (pin "D_N") (pinfunction "D-_D_N") (pintype "passive"))
    )
    (net (code "52") (name "unconnected-(J7-PadID)") (class "Default")
      (node (ref "J7") (pin "ID") (pinfunction "ID_ID") (pintype "passive"))
    )
    (net (code "53") (name "unconnected-(J16-D+-PadD_P)") (class "Default")
      (node (ref "J16") (pin "D_P") (pinfunction "D+_D_P") (pintype "passive"))
    )
    (net (code "54") (name "unconnected-(J16-D--PadD_N)") (class "Default")
      (node (ref "J16") (pin "D_N") (pinfunction "D-_D_N") (pintype "passive"))
    )
    (net (code "55") (name "unconnected-(J16-PadS)") (class "Default")
      (node (ref "J16") (pin "S") (pinfunction "S_S") (pintype "passive"))
    )
    (net (code "56") (name "unconnected-(J18-D+-PadD_P)") (class "Default")
      (node (ref "J18") (pin "D_P") (pinfunction "D+_D_P") (pintype "passive"))
    )
    (net (code "57") (name "unconnected-(J18-D--PadD_N)") (class "Default")
      (node (ref "J18") (pin "D_N") (pinfunction "D-_D_N") (pintype "passive"))
    )
    (net (code "58") (name "unconnected-(J18-PadS)") (class "Default")
      (node (ref "J18") (pin "S") (pinfunction "S_S") (pintype "passive"))
    )
    (net (code "59") (name "unconnected-(U1-~{PG}-Pad7)") (class "Default")
      (node (ref "U1") (pin "7") (pinfunction "~{PG}_7") (pintype "passive"))
    )
    (net (code "60") (name "unconnected-(U2-PG-Pad2)") (class "Default")
      (node (ref "U2") (pin "2") (pinfunction "PG_2") (pintype "passive"))
    )
    (net (code "61") (name "unconnected-(U3-PG-Pad2)") (class "Default")
      (node (ref "U3") (pin "2") (pinfunction "PG_2") (pintype "passive"))
    )
  )
)
